# PCB-ARD-DUEBOS.net
KiCad netlist of a schematic drawn in EAGLE
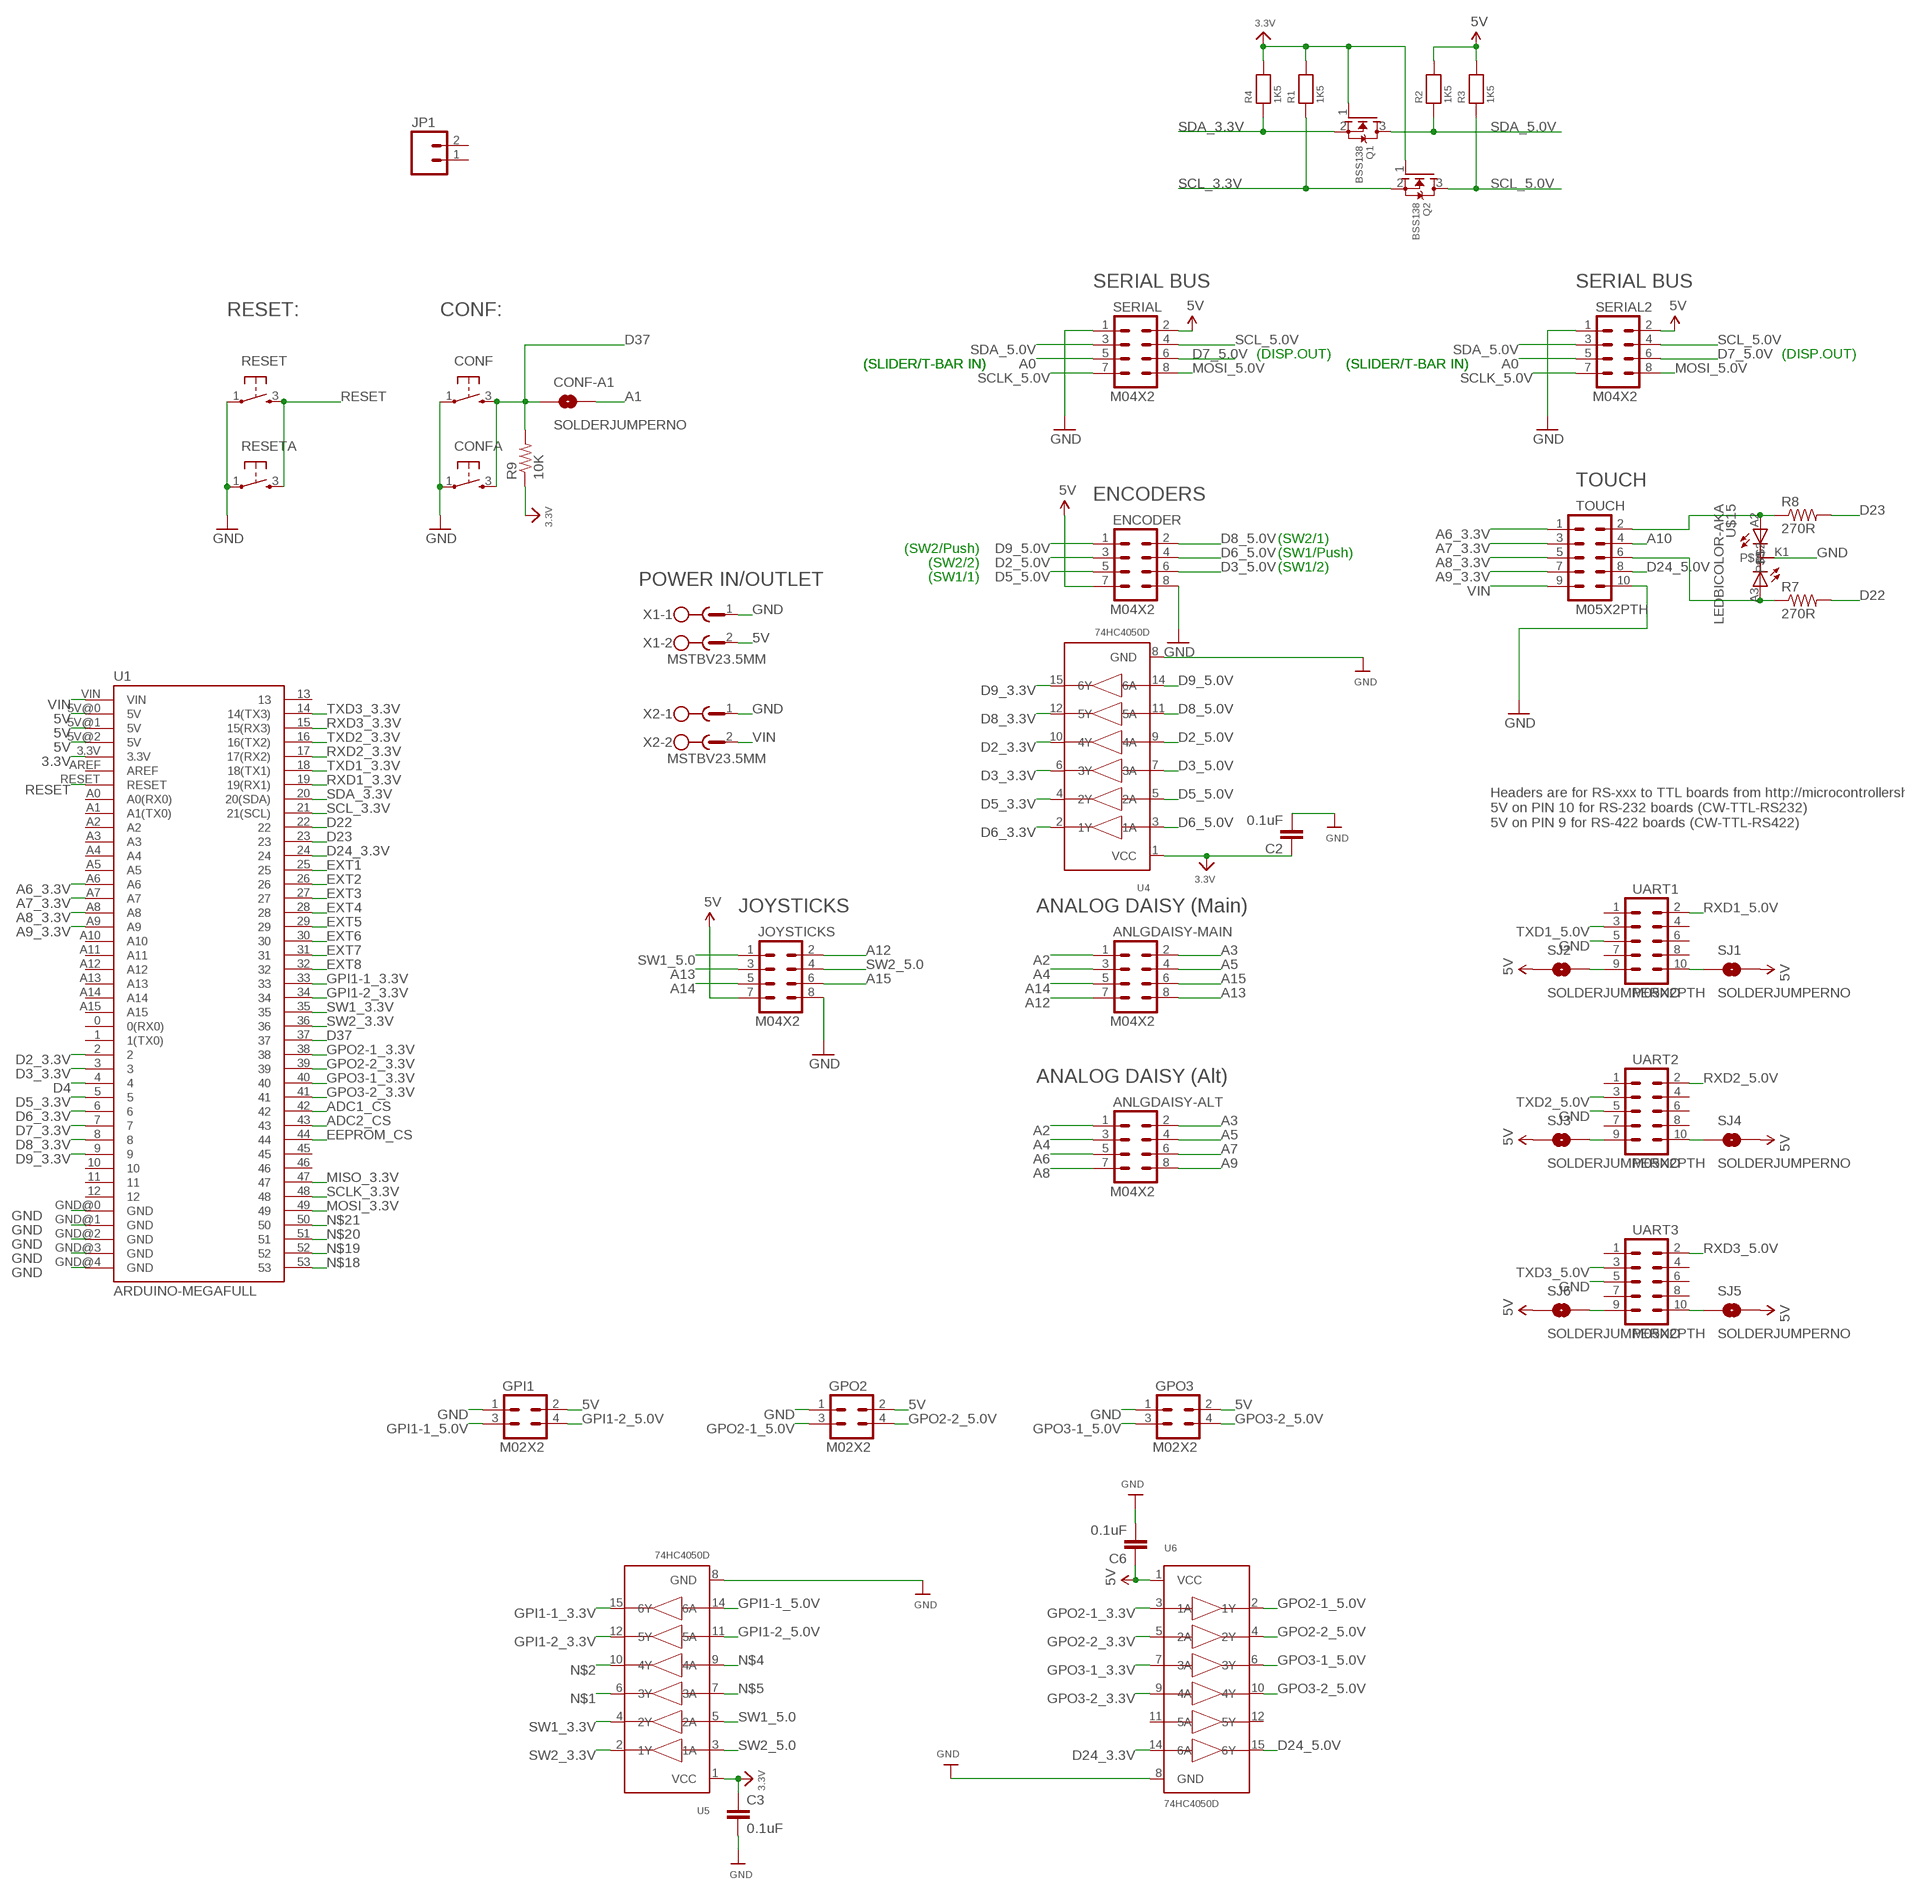
[diagram p0: schematic, sheet 1, part 1 of 2]
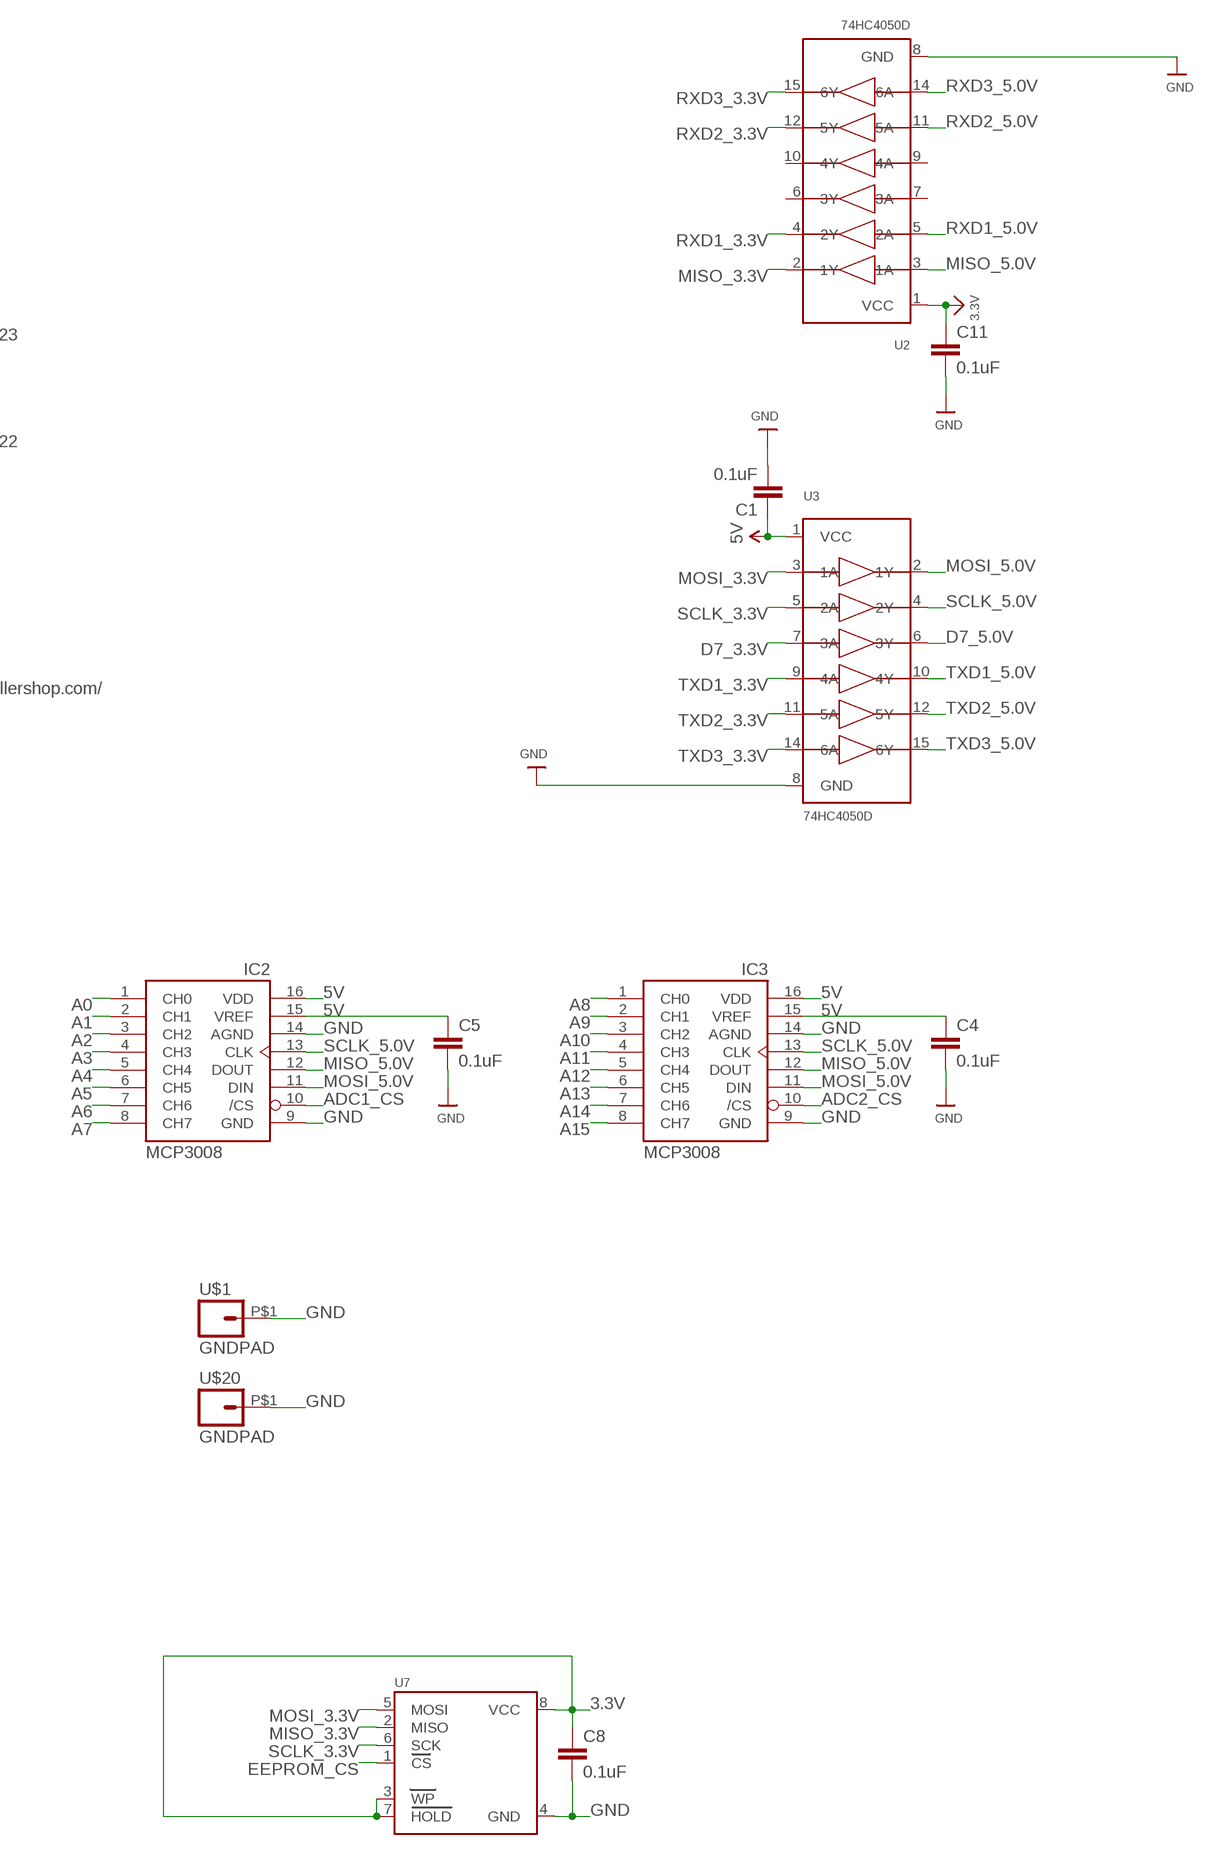
[diagram p1: schematic, sheet 1, part 2 of 2]

(export (version "E")
  (design (tool "Eeschema 10.0.6"))
  (components
    (comp (ref "ANLGDAISY-ALT")
      (value "M04X2")
      (footprint "eagle-import:2X4")
      (libsource (lib "eagle-import") (part "M04X2"))
    )
    (comp (ref "ANLGDAISY-MAIN")
      (value "M04X2")
      (footprint "eagle-import:2X4")
      (libsource (lib "eagle-import") (part "M04X2"))
    )
    (comp (ref "C1")
      (value "0.1uF")
      (footprint "eagle-import:0603-CAP")
      (libsource (lib "eagle-import") (part "CAP0603-CAP"))
    )
    (comp (ref "C2")
      (value "0.1uF")
      (footprint "eagle-import:0603-CAP")
      (libsource (lib "eagle-import") (part "CAP0603-CAP"))
    )
    (comp (ref "C3")
      (value "0.1uF")
      (footprint "eagle-import:0603-CAP")
      (libsource (lib "eagle-import") (part "CAP0603-CAP"))
    )
    (comp (ref "C4")
      (value "0.1uF")
      (footprint "eagle-import:0603-CAP")
      (libsource (lib "eagle-import") (part "CAP0603-CAP"))
    )
    (comp (ref "C5")
      (value "0.1uF")
      (footprint "eagle-import:0603-CAP")
      (libsource (lib "eagle-import") (part "CAP0603-CAP"))
    )
    (comp (ref "C6")
      (value "0.1uF")
      (footprint "eagle-import:0603-CAP")
      (libsource (lib "eagle-import") (part "CAP0603-CAP"))
    )
    (comp (ref "C8")
      (value "0.1uF")
      (footprint "eagle-import:0603-CAP")
      (libsource (lib "eagle-import") (part "CAP0603-CAP"))
    )
    (comp (ref "C11")
      (value "0.1uF")
      (footprint "eagle-import:0603-CAP")
      (libsource (lib "eagle-import") (part "CAP0603-CAP"))
    )
    (comp (ref "CONF")
      (value "TAC_SWITCH")
      (footprint "eagle-import:PUSHBUTTON")
      (libsource (lib "eagle-import") (part "TAC_SWITCH"))
    )
    (comp (ref "CONF-A1")
      (value "SOLDERJUMPERNO")
      (footprint "eagle-import:SJ_2S-NO")
      (libsource (lib "eagle-import") (part "SOLDERJUMPERNO"))
    )
    (comp (ref "CONFA")
      (value "TAC_SWITCH")
      (footprint "eagle-import:PUSHBUTTON")
      (libsource (lib "eagle-import") (part "TAC_SWITCH"))
    )
    (comp (ref "ENCODER")
      (value "M04X2")
      (footprint "eagle-import:2X4")
      (libsource (lib "eagle-import") (part "M04X2"))
    )
    (comp (ref "GPI1")
      (value "M02X2")
      (footprint "eagle-import:2X2")
      (libsource (lib "eagle-import") (part "M02X2"))
    )
    (comp (ref "GPO2")
      (value "M02X2")
      (footprint "eagle-import:2X2")
      (libsource (lib "eagle-import") (part "M02X2"))
    )
    (comp (ref "GPO3")
      (value "M02X2")
      (footprint "eagle-import:2X2")
      (libsource (lib "eagle-import") (part "M02X2"))
    )
    (comp (ref "IC2")
      (value "MCP3008SOIC")
      (footprint "eagle-import:SOIC16")
      (libsource (lib "eagle-import") (part "MCP3008SOIC"))
    )
    (comp (ref "IC3")
      (value "MCP3008SOIC")
      (footprint "eagle-import:SOIC16")
      (libsource (lib "eagle-import") (part "MCP3008SOIC"))
    )
    (comp (ref "JOYSTICKS")
      (value "M04X2")
      (footprint "eagle-import:2X4")
      (libsource (lib "eagle-import") (part "M04X2"))
    )
    (comp (ref "JP1")
      (value "M02PTH")
      (footprint "eagle-import:1X02")
      (libsource (lib "eagle-import") (part "M02PTH"))
    )
    (comp (ref "Q1")
      (value "BSS138")
      (footprint "eagle-import:SOT23-R")
      (libsource (lib "eagle-import") (part "MOSFET-NREFLOW"))
    )
    (comp (ref "Q2")
      (value "BSS138")
      (footprint "eagle-import:SOT23-R")
      (libsource (lib "eagle-import") (part "MOSFET-NREFLOW"))
    )
    (comp (ref "R1")
      (value "1K5")
      (footprint "eagle-import:0603")
      (libsource (lib "eagle-import") (part "RESISTOR0603"))
    )
    (comp (ref "R2")
      (value "1K5")
      (footprint "eagle-import:0603")
      (libsource (lib "eagle-import") (part "RESISTOR0603"))
    )
    (comp (ref "R3")
      (value "1K5")
      (footprint "eagle-import:0603")
      (libsource (lib "eagle-import") (part "RESISTOR0603"))
    )
    (comp (ref "R4")
      (value "1K5")
      (footprint "eagle-import:0603")
      (libsource (lib "eagle-import") (part "RESISTOR0603"))
    )
    (comp (ref "R7")
      (value "270R")
      (footprint "eagle-import:0603-RES")
      (libsource (lib "eagle-import") (part "RESISTOR0603-RES"))
    )
    (comp (ref "R8")
      (value "270R")
      (footprint "eagle-import:0603-RES")
      (libsource (lib "eagle-import") (part "RESISTOR0603-RES"))
    )
    (comp (ref "R9")
      (value "10K")
      (footprint "eagle-import:0603-RES")
      (libsource (lib "eagle-import") (part "RESISTOR0603-RES"))
    )
    (comp (ref "RESET")
      (value "TAC_SWITCH")
      (footprint "eagle-import:PUSHBUTTON")
      (libsource (lib "eagle-import") (part "TAC_SWITCH"))
    )
    (comp (ref "RESETA")
      (value "TAC_SWITCH")
      (footprint "eagle-import:PUSHBUTTON")
      (libsource (lib "eagle-import") (part "TAC_SWITCH"))
    )
    (comp (ref "SERIAL")
      (value "M04X2")
      (footprint "eagle-import:2X4")
      (libsource (lib "eagle-import") (part "M04X2"))
    )
    (comp (ref "SERIAL2")
      (value "M04X2")
      (footprint "eagle-import:2X4")
      (libsource (lib "eagle-import") (part "M04X2"))
    )
    (comp (ref "SJ1")
      (value "SOLDERJUMPERNO")
      (footprint "eagle-import:SJ_2S-NO")
      (libsource (lib "eagle-import") (part "SOLDERJUMPERNO"))
    )
    (comp (ref "SJ2")
      (value "SOLDERJUMPERNO")
      (footprint "eagle-import:SJ_2S-NO")
      (libsource (lib "eagle-import") (part "SOLDERJUMPERNO"))
    )
    (comp (ref "SJ3")
      (value "SOLDERJUMPERNO")
      (footprint "eagle-import:SJ_2S-NO")
      (libsource (lib "eagle-import") (part "SOLDERJUMPERNO"))
    )
    (comp (ref "SJ4")
      (value "SOLDERJUMPERNO")
      (footprint "eagle-import:SJ_2S-NO")
      (libsource (lib "eagle-import") (part "SOLDERJUMPERNO"))
    )
    (comp (ref "SJ5")
      (value "SOLDERJUMPERNO")
      (footprint "eagle-import:SJ_2S-NO")
      (libsource (lib "eagle-import") (part "SOLDERJUMPERNO"))
    )
    (comp (ref "SJ6")
      (value "SOLDERJUMPERNO")
      (footprint "eagle-import:SJ_2S-NO")
      (libsource (lib "eagle-import") (part "SOLDERJUMPERNO"))
    )
    (comp (ref "TOUCH")
      (value "M05X2PTH")
      (footprint "eagle-import:AVR_ICSP")
      (libsource (lib "eagle-import") (part "M05X2PTH"))
    )
    (comp (ref "U$1")
      (value "GNDPAD")
      (footprint "eagle-import:3.2MMPAD")
      (libsource (lib "eagle-import") (part "GNDPAD"))
    )
    (comp (ref "U$15")
      (value "LEDBICOLOR-AKA")
      (footprint "eagle-import:LED5MM-BICOLOR")
      (libsource (lib "eagle-import") (part "LEDBICOLOR-AKA"))
    )
    (comp (ref "U$20")
      (value "GNDPAD")
      (footprint "eagle-import:3.2MMPAD")
      (libsource (lib "eagle-import") (part "GNDPAD"))
    )
    (comp (ref "U1")
      (value "ARDUINO-MEGAFULL")
      (footprint "eagle-import:ARDUINO_MEGA")
      (libsource (lib "eagle-import") (part "ARDUINO-MEGAFULL"))
    )
    (comp (ref "U2")
      (value "74HC4050D")
      (footprint "eagle-import:TSSOP16")
      (libsource (lib "eagle-import") (part "74HC4050DTSSOP16"))
    )
    (comp (ref "U3")
      (value "74HC4050D")
      (footprint "eagle-import:TSSOP16")
      (libsource (lib "eagle-import") (part "74HC4050DTSSOP16"))
    )
    (comp (ref "U4")
      (value "74HC4050D")
      (footprint "eagle-import:TSSOP16")
      (libsource (lib "eagle-import") (part "74HC4050DTSSOP16"))
    )
    (comp (ref "U5")
      (value "74HC4050D")
      (footprint "eagle-import:TSSOP16")
      (libsource (lib "eagle-import") (part "74HC4050DTSSOP16"))
    )
    (comp (ref "U6")
      (value "74HC4050D")
      (footprint "eagle-import:TSSOP16")
      (libsource (lib "eagle-import") (part "74HC4050DTSSOP16"))
    )
    (comp (ref "U7")
      (value "EEPROM_SPI_AT25040ATSSOP")
      (footprint "eagle-import:TSSOP8-4.4MM")
      (libsource (lib "eagle-import") (part "EEPROM_SPI_AT25040ATSSOP"))
    )
    (comp (ref "UART1")
      (value "M05X2PTH")
      (footprint "eagle-import:AVR_ICSP")
      (libsource (lib "eagle-import") (part "M05X2PTH"))
    )
    (comp (ref "UART2")
      (value "M05X2PTH")
      (footprint "eagle-import:AVR_ICSP")
      (libsource (lib "eagle-import") (part "M05X2PTH"))
    )
    (comp (ref "UART3")
      (value "M05X2PTH")
      (footprint "eagle-import:AVR_ICSP")
      (libsource (lib "eagle-import") (part "M05X2PTH"))
    )
    (comp (ref "X1")
      (value "MSTBV23.5MM")
      (footprint "eagle-import:MSTBV2-3.5")
      (libsource (lib "eagle-import") (part "MSTBV23.5MM"))
    )
    (comp (ref "X2")
      (value "MSTBV23.5MM")
      (footprint "eagle-import:MSTBV2-3.5")
      (libsource (lib "eagle-import") (part "MSTBV23.5MM"))
    )
  )
  (nets
    (net (code "1") (name "/A0") (class "Default")
      (node (ref "IC2") (pin "1") (pinfunction "CH0_1") (pintype "input"))
      (node (ref "SERIAL") (pin "5") (pinfunction "5_5") (pintype "passive"))
      (node (ref "SERIAL2") (pin "5") (pinfunction "5_5") (pintype "passive"))
    )
    (net (code "2") (name "/A1") (class "Default")
      (node (ref "CONF-A1") (pin "2") (pinfunction "2_2") (pintype "passive"))
      (node (ref "IC2") (pin "2") (pinfunction "CH1_2") (pintype "input"))
    )
    (net (code "3") (name "/A2") (class "Default")
      (node (ref "ANLGDAISY-ALT") (pin "1") (pinfunction "1_1") (pintype "passive"))
      (node (ref "ANLGDAISY-MAIN") (pin "1") (pinfunction "1_1") (pintype "passive"))
      (node (ref "IC2") (pin "3") (pinfunction "CH2_3") (pintype "input"))
    )
    (net (code "4") (name "/A3") (class "Default")
      (node (ref "ANLGDAISY-ALT") (pin "2") (pinfunction "2_2") (pintype "passive"))
      (node (ref "ANLGDAISY-MAIN") (pin "2") (pinfunction "2_2") (pintype "passive"))
      (node (ref "IC2") (pin "4") (pinfunction "CH3_4") (pintype "input"))
    )
    (net (code "5") (name "/A4") (class "Default")
      (node (ref "ANLGDAISY-ALT") (pin "3") (pinfunction "3_3") (pintype "passive"))
      (node (ref "ANLGDAISY-MAIN") (pin "3") (pinfunction "3_3") (pintype "passive"))
      (node (ref "IC2") (pin "5") (pinfunction "CH4_5") (pintype "input"))
    )
    (net (code "6") (name "/A5") (class "Default")
      (node (ref "ANLGDAISY-ALT") (pin "4") (pinfunction "4_4") (pintype "passive"))
      (node (ref "ANLGDAISY-MAIN") (pin "4") (pinfunction "4_4") (pintype "passive"))
      (node (ref "IC2") (pin "6") (pinfunction "CH5_6") (pintype "input"))
    )
    (net (code "7") (name "/A6") (class "Default")
      (node (ref "ANLGDAISY-ALT") (pin "5") (pinfunction "5_5") (pintype "passive"))
      (node (ref "IC2") (pin "7") (pinfunction "CH6_7") (pintype "input"))
    )
    (net (code "8") (name "/A6_3.3V") (class "Default")
      (node (ref "TOUCH") (pin "1") (pinfunction "1_1") (pintype "passive"))
      (node (ref "U1") (pin "A6") (pinfunction "A6_A6") (pintype "bidirectional"))
    )
    (net (code "9") (name "/A7") (class "Default")
      (node (ref "ANLGDAISY-ALT") (pin "6") (pinfunction "6_6") (pintype "passive"))
      (node (ref "IC2") (pin "8") (pinfunction "CH7_8") (pintype "input"))
    )
    (net (code "10") (name "/A7_3.3V") (class "Default")
      (node (ref "TOUCH") (pin "3") (pinfunction "3_3") (pintype "passive"))
      (node (ref "U1") (pin "A7") (pinfunction "A7_A7") (pintype "bidirectional"))
    )
    (net (code "11") (name "/A8") (class "Default")
      (node (ref "ANLGDAISY-ALT") (pin "7") (pinfunction "7_7") (pintype "passive"))
      (node (ref "IC3") (pin "1") (pinfunction "CH0_1") (pintype "input"))
    )
    (net (code "12") (name "/A8_3.3V") (class "Default")
      (node (ref "TOUCH") (pin "5") (pinfunction "5_5") (pintype "passive"))
      (node (ref "U1") (pin "A8") (pinfunction "A8_A8") (pintype "bidirectional"))
    )
    (net (code "13") (name "/A9") (class "Default")
      (node (ref "ANLGDAISY-ALT") (pin "8") (pinfunction "8_8") (pintype "passive"))
      (node (ref "IC3") (pin "2") (pinfunction "CH1_2") (pintype "input"))
    )
    (net (code "14") (name "/A9_3.3V") (class "Default")
      (node (ref "TOUCH") (pin "7") (pinfunction "7_7") (pintype "passive"))
      (node (ref "U1") (pin "A9") (pinfunction "A9_A9") (pintype "bidirectional"))
    )
    (net (code "15") (name "/A10") (class "Default")
      (node (ref "IC3") (pin "3") (pinfunction "CH2_3") (pintype "input"))
      (node (ref "TOUCH") (pin "4") (pinfunction "4_4") (pintype "passive"))
    )
    (net (code "16") (name "/A11") (class "Default")
      (node (ref "IC3") (pin "4") (pinfunction "CH3_4") (pintype "input"))
    )
    (net (code "17") (name "/A12") (class "Default")
      (node (ref "ANLGDAISY-MAIN") (pin "7") (pinfunction "7_7") (pintype "passive"))
      (node (ref "IC3") (pin "5") (pinfunction "CH4_5") (pintype "input"))
      (node (ref "JOYSTICKS") (pin "2") (pinfunction "2_2") (pintype "passive"))
    )
    (net (code "18") (name "/A13") (class "Default")
      (node (ref "ANLGDAISY-MAIN") (pin "8") (pinfunction "8_8") (pintype "passive"))
      (node (ref "IC3") (pin "6") (pinfunction "CH5_6") (pintype "input"))
      (node (ref "JOYSTICKS") (pin "3") (pinfunction "3_3") (pintype "passive"))
    )
    (net (code "19") (name "/A14") (class "Default")
      (node (ref "ANLGDAISY-MAIN") (pin "5") (pinfunction "5_5") (pintype "passive"))
      (node (ref "IC3") (pin "7") (pinfunction "CH6_7") (pintype "input"))
      (node (ref "JOYSTICKS") (pin "5") (pinfunction "5_5") (pintype "passive"))
    )
    (net (code "20") (name "/A15") (class "Default")
      (node (ref "ANLGDAISY-MAIN") (pin "6") (pinfunction "6_6") (pintype "passive"))
      (node (ref "IC3") (pin "8") (pinfunction "CH7_8") (pintype "input"))
      (node (ref "JOYSTICKS") (pin "6") (pinfunction "6_6") (pintype "passive"))
    )
    (net (code "21") (name "/ADC1_CS") (class "Default")
      (node (ref "IC2") (pin "10") (pinfunction "/CS_10") (pintype "input"))
      (node (ref "U1") (pin "42") (pinfunction "42_42") (pintype "bidirectional"))
    )
    (net (code "22") (name "/ADC2_CS") (class "Default")
      (node (ref "IC3") (pin "10") (pinfunction "/CS_10") (pintype "input"))
      (node (ref "U1") (pin "43") (pinfunction "43_43") (pintype "bidirectional"))
    )
    (net (code "23") (name "/D2_3.3V") (class "Default")
      (node (ref "U1") (pin "2") (pinfunction "2_2") (pintype "bidirectional"))
      (node (ref "U4") (pin "10") (pinfunction "4Y_10") (pintype "bidirectional"))
    )
    (net (code "24") (name "/D2_5.0V") (class "Default")
      (node (ref "ENCODER") (pin "3") (pinfunction "3_3") (pintype "passive"))
      (node (ref "U4") (pin "9") (pinfunction "4A_9") (pintype "bidirectional"))
    )
    (net (code "25") (name "/D3_3.3V") (class "Default")
      (node (ref "U1") (pin "3") (pinfunction "3_3") (pintype "bidirectional"))
      (node (ref "U4") (pin "6") (pinfunction "3Y_6") (pintype "bidirectional"))
    )
    (net (code "26") (name "/D3_5.0V") (class "Default")
      (node (ref "ENCODER") (pin "6") (pinfunction "6_6") (pintype "passive"))
      (node (ref "U4") (pin "7") (pinfunction "3A_7") (pintype "bidirectional"))
    )
    (net (code "27") (name "/D4") (class "Default")
      (node (ref "U1") (pin "4") (pinfunction "4_4") (pintype "bidirectional"))
    )
    (net (code "28") (name "/D5_3.3V") (class "Default")
      (node (ref "U1") (pin "5") (pinfunction "5_5") (pintype "bidirectional"))
      (node (ref "U4") (pin "4") (pinfunction "2Y_4") (pintype "bidirectional"))
    )
    (net (code "29") (name "/D5_5.0V") (class "Default")
      (node (ref "ENCODER") (pin "5") (pinfunction "5_5") (pintype "passive"))
      (node (ref "U4") (pin "5") (pinfunction "2A_5") (pintype "bidirectional"))
    )
    (net (code "30") (name "/D6_3.3V") (class "Default")
      (node (ref "U1") (pin "6") (pinfunction "6_6") (pintype "bidirectional"))
      (node (ref "U4") (pin "2") (pinfunction "1Y_2") (pintype "bidirectional"))
    )
    (net (code "31") (name "/D6_5.0V") (class "Default")
      (node (ref "ENCODER") (pin "4") (pinfunction "4_4") (pintype "passive"))
      (node (ref "U4") (pin "3") (pinfunction "1A_3") (pintype "bidirectional"))
    )
    (net (code "32") (name "/D7_3.3V") (class "Default")
      (node (ref "U1") (pin "7") (pinfunction "7_7") (pintype "bidirectional"))
      (node (ref "U3") (pin "7") (pinfunction "3A_7") (pintype "bidirectional"))
    )
    (net (code "33") (name "/D7_5.0V") (class "Default")
      (node (ref "SERIAL") (pin "6") (pinfunction "6_6") (pintype "passive"))
      (node (ref "SERIAL2") (pin "6") (pinfunction "6_6") (pintype "passive"))
      (node (ref "U3") (pin "6") (pinfunction "3Y_6") (pintype "bidirectional"))
    )
    (net (code "34") (name "/D8_3.3V") (class "Default")
      (node (ref "U1") (pin "8") (pinfunction "8_8") (pintype "bidirectional"))
      (node (ref "U4") (pin "12") (pinfunction "5Y_12") (pintype "bidirectional"))
    )
    (net (code "35") (name "/D8_5.0V") (class "Default")
      (node (ref "ENCODER") (pin "2") (pinfunction "2_2") (pintype "passive"))
      (node (ref "U4") (pin "11") (pinfunction "5A_11") (pintype "bidirectional"))
    )
    (net (code "36") (name "/D9_3.3V") (class "Default")
      (node (ref "U1") (pin "9") (pinfunction "9_9") (pintype "bidirectional"))
      (node (ref "U4") (pin "15") (pinfunction "6Y_15") (pintype "bidirectional"))
    )
    (net (code "37") (name "/D9_5.0V") (class "Default")
      (node (ref "ENCODER") (pin "1") (pinfunction "1_1") (pintype "passive"))
      (node (ref "U4") (pin "14") (pinfunction "6A_14") (pintype "bidirectional"))
    )
    (net (code "38") (name "/D22") (class "Default")
      (node (ref "R7") (pin "2") (pinfunction "2_2") (pintype "passive"))
      (node (ref "U1") (pin "22") (pinfunction "22_22") (pintype "bidirectional"))
    )
    (net (code "39") (name "/D23") (class "Default")
      (node (ref "R8") (pin "2") (pinfunction "2_2") (pintype "passive"))
      (node (ref "U1") (pin "23") (pinfunction "23_23") (pintype "bidirectional"))
    )
    (net (code "40") (name "/D24_3.3V") (class "Default")
      (node (ref "U1") (pin "24") (pinfunction "24_24") (pintype "bidirectional"))
      (node (ref "U6") (pin "14") (pinfunction "6A_14") (pintype "bidirectional"))
    )
    (net (code "41") (name "/D24_5.0V") (class "Default")
      (node (ref "TOUCH") (pin "8") (pinfunction "8_8") (pintype "passive"))
      (node (ref "U6") (pin "15") (pinfunction "6Y_15") (pintype "bidirectional"))
    )
    (net (code "42") (name "/D37") (class "Default")
      (node (ref "CONF") (pin "3") (pinfunction "3_3") (pintype "passive"))
      (node (ref "CONF-A1") (pin "1") (pinfunction "1_1") (pintype "passive"))
      (node (ref "CONFA") (pin "3") (pinfunction "3_3") (pintype "passive"))
      (node (ref "R9") (pin "2") (pinfunction "2_2") (pintype "passive"))
      (node (ref "U1") (pin "37") (pinfunction "37_37") (pintype "bidirectional"))
    )
    (net (code "43") (name "/EEPROM_CS") (class "Default")
      (node (ref "U1") (pin "44") (pinfunction "44_44") (pintype "bidirectional"))
      (node (ref "U7") (pin "1") (pinfunction "CS_1") (pintype "bidirectional"))
    )
    (net (code "44") (name "/EXT1") (class "Default")
      (node (ref "U1") (pin "25") (pinfunction "25_25") (pintype "bidirectional"))
    )
    (net (code "45") (name "/EXT2") (class "Default")
      (node (ref "U1") (pin "26") (pinfunction "26_26") (pintype "bidirectional"))
    )
    (net (code "46") (name "/EXT3") (class "Default")
      (node (ref "U1") (pin "27") (pinfunction "27_27") (pintype "bidirectional"))
    )
    (net (code "47") (name "/EXT4") (class "Default")
      (node (ref "U1") (pin "28") (pinfunction "28_28") (pintype "bidirectional"))
    )
    (net (code "48") (name "/EXT5") (class "Default")
      (node (ref "U1") (pin "29") (pinfunction "29_29") (pintype "bidirectional"))
    )
    (net (code "49") (name "/EXT6") (class "Default")
      (node (ref "U1") (pin "30") (pinfunction "30_30") (pintype "bidirectional"))
    )
    (net (code "50") (name "/EXT7") (class "Default")
      (node (ref "U1") (pin "31") (pinfunction "31_31") (pintype "bidirectional"))
    )
    (net (code "51") (name "/EXT8") (class "Default")
      (node (ref "U1") (pin "32") (pinfunction "32_32") (pintype "bidirectional"))
    )
    (net (code "52") (name "/GPI1-1_3.3V") (class "Default")
      (node (ref "U1") (pin "33") (pinfunction "33_33") (pintype "bidirectional"))
      (node (ref "U5") (pin "15") (pinfunction "6Y_15") (pintype "bidirectional"))
    )
    (net (code "53") (name "/GPI1-1_5.0V") (class "Default")
      (node (ref "GPI1") (pin "3") (pinfunction "3_3") (pintype "passive"))
      (node (ref "U5") (pin "14") (pinfunction "6A_14") (pintype "bidirectional"))
    )
    (net (code "54") (name "/GPI1-2_3.3V") (class "Default")
      (node (ref "U1") (pin "34") (pinfunction "34_34") (pintype "bidirectional"))
      (node (ref "U5") (pin "12") (pinfunction "5Y_12") (pintype "bidirectional"))
    )
    (net (code "55") (name "/GPI1-2_5.0V") (class "Default")
      (node (ref "GPI1") (pin "4") (pinfunction "4_4") (pintype "passive"))
      (node (ref "U5") (pin "11") (pinfunction "5A_11") (pintype "bidirectional"))
    )
    (net (code "56") (name "/GPO2-1_3.3V") (class "Default")
      (node (ref "U1") (pin "38") (pinfunction "38_38") (pintype "bidirectional"))
      (node (ref "U6") (pin "3") (pinfunction "1A_3") (pintype "bidirectional"))
    )
    (net (code "57") (name "/GPO2-1_5.0V") (class "Default")
      (node (ref "GPO2") (pin "3") (pinfunction "3_3") (pintype "passive"))
      (node (ref "U6") (pin "2") (pinfunction "1Y_2") (pintype "bidirectional"))
    )
    (net (code "58") (name "/GPO2-2_3.3V") (class "Default")
      (node (ref "U1") (pin "39") (pinfunction "39_39") (pintype "bidirectional"))
      (node (ref "U6") (pin "5") (pinfunction "2A_5") (pintype "bidirectional"))
    )
    (net (code "59") (name "/GPO2-2_5.0V") (class "Default")
      (node (ref "GPO2") (pin "4") (pinfunction "4_4") (pintype "passive"))
      (node (ref "U6") (pin "4") (pinfunction "2Y_4") (pintype "bidirectional"))
    )
    (net (code "60") (name "/GPO3-1_3.3V") (class "Default")
      (node (ref "U1") (pin "40") (pinfunction "40_40") (pintype "bidirectional"))
      (node (ref "U6") (pin "7") (pinfunction "3A_7") (pintype "bidirectional"))
    )
    (net (code "61") (name "/GPO3-1_5.0V") (class "Default")
      (node (ref "GPO3") (pin "3") (pinfunction "3_3") (pintype "passive"))
      (node (ref "U6") (pin "6") (pinfunction "3Y_6") (pintype "bidirectional"))
    )
    (net (code "62") (name "/GPO3-2_3.3V") (class "Default")
      (node (ref "U1") (pin "41") (pinfunction "41_41") (pintype "bidirectional"))
      (node (ref "U6") (pin "9") (pinfunction "4A_9") (pintype "bidirectional"))
    )
    (net (code "63") (name "/GPO3-2_5.0V") (class "Default")
      (node (ref "GPO3") (pin "4") (pinfunction "4_4") (pintype "passive"))
      (node (ref "U6") (pin "10") (pinfunction "4Y_10") (pintype "bidirectional"))
    )
    (net (code "64") (name "/MISO_3.3V") (class "Default")
      (node (ref "U1") (pin "47") (pinfunction "47_47") (pintype "bidirectional"))
      (node (ref "U2") (pin "2") (pinfunction "1Y_2") (pintype "bidirectional"))
      (node (ref "U7") (pin "2") (pinfunction "MISO_2") (pintype "bidirectional"))
    )
    (net (code "65") (name "/MISO_5.0V") (class "Default")
      (node (ref "IC2") (pin "12") (pinfunction "DOUT_12") (pintype "output"))
      (node (ref "IC3") (pin "12") (pinfunction "DOUT_12") (pintype "output"))
      (node (ref "U2") (pin "3") (pinfunction "1A_3") (pintype "bidirectional"))
    )
    (net (code "66") (name "/MOSI_3.3V") (class "Default")
      (node (ref "U1") (pin "49") (pinfunction "49_49") (pintype "bidirectional"))
      (node (ref "U3") (pin "3") (pinfunction "1A_3") (pintype "bidirectional"))
      (node (ref "U7") (pin "5") (pinfunction "MOSI_5") (pintype "bidirectional"))
    )
    (net (code "67") (name "/MOSI_5.0V") (class "Default")
      (node (ref "IC2") (pin "11") (pinfunction "DIN_11") (pintype "input"))
      (node (ref "IC3") (pin "11") (pinfunction "DIN_11") (pintype "input"))
      (node (ref "SERIAL") (pin "8") (pinfunction "8_8") (pintype "passive"))
      (node (ref "SERIAL2") (pin "8") (pinfunction "8_8") (pintype "passive"))
      (node (ref "U3") (pin "2") (pinfunction "1Y_2") (pintype "bidirectional"))
    )
    (net (code "68") (name "/N$1") (class "Default")
      (node (ref "U5") (pin "6") (pinfunction "3Y_6") (pintype "bidirectional"))
    )
    (net (code "69") (name "/N$2") (class "Default")
      (node (ref "U5") (pin "10") (pinfunction "4Y_10") (pintype "bidirectional"))
    )
    (net (code "70") (name "/N$4") (class "Default")
      (node (ref "U5") (pin "9") (pinfunction "4A_9") (pintype "bidirectional"))
    )
    (net (code "71") (name "/N$5") (class "Default")
      (node (ref "U5") (pin "7") (pinfunction "3A_7") (pintype "bidirectional"))
    )
    (net (code "72") (name "/N$18") (class "Default")
      (node (ref "U1") (pin "53") (pinfunction "53_53") (pintype "bidirectional"))
    )
    (net (code "73") (name "/N$19") (class "Default")
      (node (ref "U1") (pin "52") (pinfunction "52_52") (pintype "bidirectional"))
    )
    (net (code "74") (name "/N$20") (class "Default")
      (node (ref "U1") (pin "51") (pinfunction "51_51") (pintype "bidirectional"))
    )
    (net (code "75") (name "/N$21") (class "Default")
      (node (ref "U1") (pin "50") (pinfunction "50_50") (pintype "bidirectional"))
    )
    (net (code "76") (name "/RESET") (class "Default")
      (node (ref "RESET") (pin "3") (pinfunction "3_3") (pintype "passive"))
      (node (ref "RESETA") (pin "3") (pinfunction "3_3") (pintype "passive"))
      (node (ref "U1") (pin "RESET") (pinfunction "RESET_RESET") (pintype "bidirectional"))
    )
    (net (code "77") (name "/RXD1_3.3V") (class "Default")
      (node (ref "U1") (pin "19") (pinfunction "19(RX1)_19") (pintype "bidirectional"))
      (node (ref "U2") (pin "4") (pinfunction "2Y_4") (pintype "bidirectional"))
    )
    (net (code "78") (name "/RXD1_5.0V") (class "Default")
      (node (ref "U2") (pin "5") (pinfunction "2A_5") (pintype "bidirectional"))
      (node (ref "UART1") (pin "2") (pinfunction "2_2") (pintype "passive"))
    )
    (net (code "79") (name "/RXD2_3.3V") (class "Default")
      (node (ref "U1") (pin "17") (pinfunction "17(RX2)_17") (pintype "bidirectional"))
      (node (ref "U2") (pin "12") (pinfunction "5Y_12") (pintype "bidirectional"))
    )
    (net (code "80") (name "/RXD2_5.0V") (class "Default")
      (node (ref "U2") (pin "11") (pinfunction "5A_11") (pintype "bidirectional"))
      (node (ref "UART2") (pin "2") (pinfunction "2_2") (pintype "passive"))
    )
    (net (code "81") (name "/RXD3_3.3V") (class "Default")
      (node (ref "U1") (pin "15") (pinfunction "15(RX3)_15") (pintype "bidirectional"))
      (node (ref "U2") (pin "15") (pinfunction "6Y_15") (pintype "bidirectional"))
    )
    (net (code "82") (name "/RXD3_5.0V") (class "Default")
      (node (ref "U2") (pin "14") (pinfunction "6A_14") (pintype "bidirectional"))
      (node (ref "UART3") (pin "2") (pinfunction "2_2") (pintype "passive"))
    )
    (net (code "83") (name "/SCLK_3.3V") (class "Default")
      (node (ref "U1") (pin "48") (pinfunction "48_48") (pintype "bidirectional"))
      (node (ref "U3") (pin "5") (pinfunction "2A_5") (pintype "bidirectional"))
      (node (ref "U7") (pin "6") (pinfunction "SCK_6") (pintype "bidirectional"))
    )
    (net (code "84") (name "/SCLK_5.0V") (class "Default")
      (node (ref "IC2") (pin "13") (pinfunction "CLK_13") (pintype "input"))
      (node (ref "IC3") (pin "13") (pinfunction "CLK_13") (pintype "input"))
      (node (ref "SERIAL") (pin "7") (pinfunction "7_7") (pintype "passive"))
      (node (ref "SERIAL2") (pin "7") (pinfunction "7_7") (pintype "passive"))
      (node (ref "U3") (pin "4") (pinfunction "2Y_4") (pintype "bidirectional"))
    )
    (net (code "85") (name "/SCL_3.3V") (class "Default")
      (node (ref "Q2") (pin "2") (pinfunction "S_2") (pintype "bidirectional"))
      (node (ref "R1") (pin "1") (pinfunction "1_1") (pintype "passive"))
      (node (ref "U1") (pin "21") (pinfunction "21(SCL)_21") (pintype "bidirectional"))
    )
    (net (code "86") (name "/SCL_5.0V") (class "Default")
      (node (ref "Q2") (pin "3") (pinfunction "D_3") (pintype "bidirectional"))
      (node (ref "R3") (pin "1") (pinfunction "1_1") (pintype "passive"))
      (node (ref "SERIAL") (pin "4") (pinfunction "4_4") (pintype "passive"))
      (node (ref "SERIAL2") (pin "4") (pinfunction "4_4") (pintype "passive"))
    )
    (net (code "87") (name "/SDA_3.3V") (class "Default")
      (node (ref "Q1") (pin "2") (pinfunction "S_2") (pintype "bidirectional"))
      (node (ref "R4") (pin "1") (pinfunction "1_1") (pintype "passive"))
      (node (ref "U1") (pin "20") (pinfunction "20(SDA)_20") (pintype "bidirectional"))
    )
    (net (code "88") (name "/SDA_5.0V") (class "Default")
      (node (ref "Q1") (pin "3") (pinfunction "D_3") (pintype "bidirectional"))
      (node (ref "R2") (pin "1") (pinfunction "1_1") (pintype "passive"))
      (node (ref "SERIAL") (pin "3") (pinfunction "3_3") (pintype "passive"))
      (node (ref "SERIAL2") (pin "3") (pinfunction "3_3") (pintype "passive"))
    )
    (net (code "89") (name "/SW1_3.3V") (class "Default")
      (node (ref "U1") (pin "35") (pinfunction "35_35") (pintype "bidirectional"))
      (node (ref "U5") (pin "4") (pinfunction "2Y_4") (pintype "bidirectional"))
    )
    (net (code "90") (name "/SW1_5.0") (class "Default")
      (node (ref "JOYSTICKS") (pin "1") (pinfunction "1_1") (pintype "passive"))
      (node (ref "U5") (pin "5") (pinfunction "2A_5") (pintype "bidirectional"))
    )
    (net (code "91") (name "/SW2_3.3V") (class "Default")
      (node (ref "U1") (pin "36") (pinfunction "36_36") (pintype "bidirectional"))
      (node (ref "U5") (pin "2") (pinfunction "1Y_2") (pintype "bidirectional"))
    )
    (net (code "92") (name "/SW2_5.0") (class "Default")
      (node (ref "JOYSTICKS") (pin "4") (pinfunction "4_4") (pintype "passive"))
      (node (ref "U5") (pin "3") (pinfunction "1A_3") (pintype "bidirectional"))
    )
    (net (code "93") (name "/TXD1_3.3V") (class "Default")
      (node (ref "U1") (pin "18") (pinfunction "18(TX1)_18") (pintype "bidirectional"))
      (node (ref "U3") (pin "9") (pinfunction "4A_9") (pintype "bidirectional"))
    )
    (net (code "94") (name "/TXD1_5.0V") (class "Default")
      (node (ref "U3") (pin "10") (pinfunction "4Y_10") (pintype "bidirectional"))
      (node (ref "UART1") (pin "3") (pinfunction "3_3") (pintype "passive"))
    )
    (net (code "95") (name "/TXD2_3.3V") (class "Default")
      (node (ref "U1") (pin "16") (pinfunction "16(TX2)_16") (pintype "bidirectional"))
      (node (ref "U3") (pin "11") (pinfunction "5A_11") (pintype "bidirectional"))
    )
    (net (code "96") (name "/TXD2_5.0V") (class "Default")
      (node (ref "U3") (pin "12") (pinfunction "5Y_12") (pintype "bidirectional"))
      (node (ref "UART2") (pin "3") (pinfunction "3_3") (pintype "passive"))
    )
    (net (code "97") (name "/TXD3_3.3V") (class "Default")
      (node (ref "U1") (pin "14") (pinfunction "14(TX3)_14") (pintype "bidirectional"))
      (node (ref "U3") (pin "14") (pinfunction "6A_14") (pintype "bidirectional"))
    )
    (net (code "98") (name "/TXD3_5.0V") (class "Default")
      (node (ref "U3") (pin "15") (pinfunction "6Y_15") (pintype "bidirectional"))
      (node (ref "UART3") (pin "3") (pinfunction "3_3") (pintype "passive"))
    )
    (net (code "99") (name "/VIN") (class "Default")
      (node (ref "TOUCH") (pin "9") (pinfunction "9_9") (pintype "passive"))
      (node (ref "U1") (pin "VIN") (pinfunction "VIN_VIN") (pintype "bidirectional"))
      (node (ref "X2") (pin "2") (pinfunction "1_2") (pintype "passive"))
    )
    (net (code "100") (name "3.3V") (class "Default")
      (node (ref "C11") (pin "1") (pinfunction "1_1") (pintype "passive"))
      (node (ref "C2") (pin "1") (pinfunction "1_1") (pintype "passive"))
      (node (ref "C3") (pin "1") (pinfunction "1_1") (pintype "passive"))
      (node (ref "C8") (pin "1") (pinfunction "1_1") (pintype "passive"))
      (node (ref "Q1") (pin "1") (pinfunction "G_1") (pintype "bidirectional"))
      (node (ref "Q2") (pin "1") (pinfunction "G_1") (pintype "bidirectional"))
      (node (ref "R1") (pin "2") (pinfunction "2_2") (pintype "passive"))
      (node (ref "R4") (pin "2") (pinfunction "2_2") (pintype "passive"))
      (node (ref "R9") (pin "1") (pinfunction "1_1") (pintype "passive"))
      (node (ref "U1") (pin "3.3V") (pinfunction "3.3V_3.3V") (pintype "bidirectional"))
      (node (ref "U2") (pin "1") (pinfunction "VCC_1") (pintype "bidirectional"))
      (node (ref "U4") (pin "1") (pinfunction "VCC_1") (pintype "bidirectional"))
      (node (ref "U5") (pin "1") (pinfunction "VCC_1") (pintype "bidirectional"))
      (node (ref "U7") (pin "3") (pinfunction "WP_3") (pintype "bidirectional"))
      (node (ref "U7") (pin "7") (pinfunction "HOLD_7") (pintype "bidirectional"))
      (node (ref "U7") (pin "8") (pinfunction "VCC_8") (pintype "power_in"))
    )
    (net (code "101") (name "5V") (class "Default")
      (node (ref "C1") (pin "1") (pinfunction "1_1") (pintype "passive"))
      (node (ref "C4") (pin "1") (pinfunction "1_1") (pintype "passive"))
      (node (ref "C5") (pin "1") (pinfunction "1_1") (pintype "passive"))
      (node (ref "C6") (pin "1") (pinfunction "1_1") (pintype "passive"))
      (node (ref "ENCODER") (pin "7") (pinfunction "7_7") (pintype "passive"))
      (node (ref "GPI1") (pin "2") (pinfunction "2_2") (pintype "passive"))
      (node (ref "GPO2") (pin "2") (pinfunction "2_2") (pintype "passive"))
      (node (ref "GPO3") (pin "2") (pinfunction "2_2") (pintype "passive"))
      (node (ref "IC2") (pin "15") (pinfunction "VREF_15") (pintype "input"))
      (node (ref "IC2") (pin "16") (pinfunction "VDD_16") (pintype "power_in"))
      (node (ref "IC3") (pin "15") (pinfunction "VREF_15") (pintype "input"))
      (node (ref "IC3") (pin "16") (pinfunction "VDD_16") (pintype "power_in"))
      (node (ref "JOYSTICKS") (pin "7") (pinfunction "7_7") (pintype "passive"))
      (node (ref "R2") (pin "2") (pinfunction "2_2") (pintype "passive"))
      (node (ref "R3") (pin "2") (pinfunction "2_2") (pintype "passive"))
      (node (ref "SERIAL") (pin "2") (pinfunction "2_2") (pintype "passive"))
      (node (ref "SERIAL2") (pin "2") (pinfunction "2_2") (pintype "passive"))
      (node (ref "SJ1") (pin "2") (pinfunction "2_2") (pintype "passive"))
      (node (ref "SJ2") (pin "1") (pinfunction "1_1") (pintype "passive"))
      (node (ref "SJ3") (pin "1") (pinfunction "1_1") (pintype "passive"))
      (node (ref "SJ4") (pin "2") (pinfunction "2_2") (pintype "passive"))
      (node (ref "SJ5") (pin "2") (pinfunction "2_2") (pintype "passive"))
      (node (ref "SJ6") (pin "1") (pinfunction "1_1") (pintype "passive"))
      (node (ref "U1") (pin "5V@0") (pinfunction "5V_5V@0") (pintype "bidirectional"))
      (node (ref "U1") (pin "5V@1") (pinfunction "5V_5V@1") (pintype "bidirectional"))
      (node (ref "U1") (pin "5V@2") (pinfunction "5V_5V@2") (pintype "bidirectional"))
      (node (ref "U3") (pin "1") (pinfunction "VCC_1") (pintype "bidirectional"))
      (node (ref "U6") (pin "1") (pinfunction "VCC_1") (pintype "bidirectional"))
      (node (ref "X1") (pin "2") (pinfunction "1_2") (pintype "passive"))
    )
    (net (code "102") (name "GND") (class "Default")
      (node (ref "C1") (pin "2") (pinfunction "2_2") (pintype "passive"))
      (node (ref "C11") (pin "2") (pinfunction "2_2") (pintype "passive"))
      (node (ref "C2") (pin "2") (pinfunction "2_2") (pintype "passive"))
      (node (ref "C3") (pin "2") (pinfunction "2_2") (pintype "passive"))
      (node (ref "C4") (pin "2") (pinfunction "2_2") (pintype "passive"))
      (node (ref "C5") (pin "2") (pinfunction "2_2") (pintype "passive"))
      (node (ref "C6") (pin "2") (pinfunction "2_2") (pintype "passive"))
      (node (ref "C8") (pin "2") (pinfunction "2_2") (pintype "passive"))
      (node (ref "CONF") (pin "1") (pinfunction "1_1") (pintype "passive"))
      (node (ref "CONFA") (pin "1") (pinfunction "1_1") (pintype "passive"))
      (node (ref "ENCODER") (pin "8") (pinfunction "8_8") (pintype "passive"))
      (node (ref "GPI1") (pin "1") (pinfunction "1_1") (pintype "passive"))
      (node (ref "GPO2") (pin "1") (pinfunction "1_1") (pintype "passive"))
      (node (ref "GPO3") (pin "1") (pinfunction "1_1") (pintype "passive"))
      (node (ref "IC2") (pin "14") (pinfunction "AGND_14") (pintype "power_in"))
      (node (ref "IC2") (pin "9") (pinfunction "GND_9") (pintype "power_in"))
      (node (ref "IC3") (pin "14") (pinfunction "AGND_14") (pintype "power_in"))
      (node (ref "IC3") (pin "9") (pinfunction "GND_9") (pintype "power_in"))
      (node (ref "JOYSTICKS") (pin "8") (pinfunction "8_8") (pintype "passive"))
      (node (ref "RESET") (pin "1") (pinfunction "1_1") (pintype "passive"))
      (node (ref "RESETA") (pin "1") (pinfunction "1_1") (pintype "passive"))
      (node (ref "SERIAL") (pin "1") (pinfunction "1_1") (pintype "passive"))
      (node (ref "SERIAL2") (pin "1") (pinfunction "1_1") (pintype "passive"))
      (node (ref "TOUCH") (pin "10") (pinfunction "10_10") (pintype "passive"))
      (node (ref "U$1") (pin "P$1") (pinfunction "1_P$1") (pintype "passive"))
      (node (ref "U$15") (pin "K1") (pinfunction "P$1_K1") (pintype "bidirectional"))
      (node (ref "U$20") (pin "P$1") (pinfunction "1_P$1") (pintype "passive"))
      (node (ref "U1") (pin "GND@0") (pinfunction "GND_GND@0") (pintype "bidirectional"))
      (node (ref "U1") (pin "GND@1") (pinfunction "GND_GND@1") (pintype "bidirectional"))
      (node (ref "U1") (pin "GND@2") (pinfunction "GND_GND@2") (pintype "bidirectional"))
      (node (ref "U1") (pin "GND@3") (pinfunction "GND_GND@3") (pintype "bidirectional"))
      (node (ref "U1") (pin "GND@4") (pinfunction "GND_GND@4") (pintype "bidirectional"))
      (node (ref "U2") (pin "8") (pinfunction "GND_8") (pintype "bidirectional"))
      (node (ref "U3") (pin "8") (pinfunction "GND_8") (pintype "bidirectional"))
      (node (ref "U4") (pin "8") (pinfunction "GND_8") (pintype "bidirectional"))
      (node (ref "U5") (pin "8") (pinfunction "GND_8") (pintype "bidirectional"))
      (node (ref "U6") (pin "8") (pinfunction "GND_8") (pintype "bidirectional"))
      (node (ref "U7") (pin "4") (pinfunction "GND_4") (pintype "power_in"))
      (node (ref "UART1") (pin "5") (pinfunction "5_5") (pintype "passive"))
      (node (ref "UART2") (pin "5") (pinfunction "5_5") (pintype "passive"))
      (node (ref "UART3") (pin "5") (pinfunction "5_5") (pintype "passive"))
      (node (ref "X1") (pin "1") (pinfunction "1_1") (pintype "passive"))
      (node (ref "X2") (pin "1") (pinfunction "1_1") (pintype "passive"))
    )
    (net (code "103") (name "Net-(SJ1-Pad1)") (class "Default")
      (node (ref "SJ1") (pin "1") (pinfunction "1_1") (pintype "passive"))
      (node (ref "UART1") (pin "10") (pinfunction "10_10") (pintype "passive"))
    )
    (net (code "104") (name "Net-(SJ2-Pad2)") (class "Default")
      (node (ref "SJ2") (pin "2") (pinfunction "2_2") (pintype "passive"))
      (node (ref "UART1") (pin "9") (pinfunction "9_9") (pintype "passive"))
    )
    (net (code "105") (name "Net-(SJ3-Pad2)") (class "Default")
      (node (ref "SJ3") (pin "2") (pinfunction "2_2") (pintype "passive"))
      (node (ref "UART2") (pin "9") (pinfunction "9_9") (pintype "passive"))
    )
    (net (code "106") (name "Net-(SJ4-Pad1)") (class "Default")
      (node (ref "SJ4") (pin "1") (pinfunction "1_1") (pintype "passive"))
      (node (ref "UART2") (pin "10") (pinfunction "10_10") (pintype "passive"))
    )
    (net (code "107") (name "Net-(SJ5-Pad1)") (class "Default")
      (node (ref "SJ5") (pin "1") (pinfunction "1_1") (pintype "passive"))
      (node (ref "UART3") (pin "10") (pinfunction "10_10") (pintype "passive"))
    )
    (net (code "108") (name "Net-(SJ6-Pad2)") (class "Default")
      (node (ref "SJ6") (pin "2") (pinfunction "2_2") (pintype "passive"))
      (node (ref "UART3") (pin "9") (pinfunction "9_9") (pintype "passive"))
    )
    (net (code "109") (name "Net-(U$15-P$2)") (class "Default")
      (node (ref "R8") (pin "1") (pinfunction "1_1") (pintype "passive"))
      (node (ref "TOUCH") (pin "2") (pinfunction "2_2") (pintype "passive"))
      (node (ref "U$15") (pin "A2") (pinfunction "P$2_A2") (pintype "bidirectional"))
    )
    (net (code "110") (name "Net-(U$15-P$3)") (class "Default")
      (node (ref "R7") (pin "1") (pinfunction "1_1") (pintype "passive"))
      (node (ref "TOUCH") (pin "6") (pinfunction "6_6") (pintype "passive"))
      (node (ref "U$15") (pin "A3") (pinfunction "P$3_A3") (pintype "bidirectional"))
    )
    (net (code "111") (name "unconnected-(JP1-Pad1)") (class "Default")
      (node (ref "JP1") (pin "1") (pinfunction "1_1") (pintype "passive"))
    )
    (net (code "112") (name "unconnected-(JP1-Pad2)") (class "Default")
      (node (ref "JP1") (pin "2") (pinfunction "2_2") (pintype "passive"))
    )
    (net (code "113") (name "unconnected-(U1-0(RX0)-Pad0)") (class "Default")
      (node (ref "U1") (pin "0") (pinfunction "0(RX0)_0") (pintype "bidirectional"))
    )
    (net (code "114") (name "unconnected-(U1-1(TX0)-Pad1)") (class "Default")
      (node (ref "U1") (pin "1") (pinfunction "1(TX0)_1") (pintype "bidirectional"))
    )
    (net (code "115") (name "unconnected-(U1-A0(RX0)-PadA0)") (class "Default")
      (node (ref "U1") (pin "A0") (pinfunction "A0(RX0)_A0") (pintype "bidirectional"))
    )
    (net (code "116") (name "unconnected-(U1-A1(TX0)-PadA1)") (class "Default")
      (node (ref "U1") (pin "A1") (pinfunction "A1(TX0)_A1") (pintype "bidirectional"))
    )
    (net (code "117") (name "unconnected-(U1-Pad10)") (class "Default")
      (node (ref "U1") (pin "10") (pinfunction "10_10") (pintype "bidirectional"))
    )
    (net (code "118") (name "unconnected-(U1-Pad11)") (class "Default")
      (node (ref "U1") (pin "11") (pinfunction "11_11") (pintype "bidirectional"))
    )
    (net (code "119") (name "unconnected-(U1-Pad12)") (class "Default")
      (node (ref "U1") (pin "12") (pinfunction "12_12") (pintype "bidirectional"))
    )
    (net (code "120") (name "unconnected-(U1-Pad13)") (class "Default")
      (node (ref "U1") (pin "13") (pinfunction "13_13") (pintype "bidirectional"))
    )
    (net (code "121") (name "unconnected-(U1-Pad45)") (class "Default")
      (node (ref "U1") (pin "45") (pinfunction "45_45") (pintype "bidirectional"))
    )
    (net (code "122") (name "unconnected-(U1-Pad46)") (class "Default")
      (node (ref "U1") (pin "46") (pinfunction "46_46") (pintype "bidirectional"))
    )
    (net (code "123") (name "unconnected-(U1-PadA2)") (class "Default")
      (node (ref "U1") (pin "A2") (pinfunction "A2_A2") (pintype "bidirectional"))
    )
    (net (code "124") (name "unconnected-(U1-PadA3)") (class "Default")
      (node (ref "U1") (pin "A3") (pinfunction "A3_A3") (pintype "bidirectional"))
    )
    (net (code "125") (name "unconnected-(U1-PadA4)") (class "Default")
      (node (ref "U1") (pin "A4") (pinfunction "A4_A4") (pintype "bidirectional"))
    )
    (net (code "126") (name "unconnected-(U1-PadA5)") (class "Default")
      (node (ref "U1") (pin "A5") (pinfunction "A5_A5") (pintype "bidirectional"))
    )
    (net (code "127") (name "unconnected-(U1-PadA10)") (class "Default")
      (node (ref "U1") (pin "A10") (pinfunction "A10_A10") (pintype "bidirectional"))
    )
    (net (code "128") (name "unconnected-(U1-PadA11)") (class "Default")
      (node (ref "U1") (pin "A11") (pinfunction "A11_A11") (pintype "bidirectional"))
    )
    (net (code "129") (name "unconnected-(U1-PadA12)") (class "Default")
      (node (ref "U1") (pin "A12") (pinfunction "A12_A12") (pintype "bidirectional"))
    )
    (net (code "130") (name "unconnected-(U1-PadA13)") (class "Default")
      (node (ref "U1") (pin "A13") (pinfunction "A13_A13") (pintype "bidirectional"))
    )
    (net (code "131") (name "unconnected-(U1-PadA14)") (class "Default")
      (node (ref "U1") (pin "A14") (pinfunction "A14_A14") (pintype "bidirectional"))
    )
    (net (code "132") (name "unconnected-(U1-PadA15)") (class "Default")
      (node (ref "U1") (pin "A15") (pinfunction "A15_A15") (pintype "bidirectional"))
    )
    (net (code "133") (name "unconnected-(U1-PadAREF)") (class "Default")
      (node (ref "U1") (pin "AREF") (pinfunction "AREF_AREF") (pintype "bidirectional"))
    )
    (net (code "134") (name "unconnected-(U2-3A-Pad7)") (class "Default")
      (node (ref "U2") (pin "7") (pinfunction "3A_7") (pintype "bidirectional"))
    )
    (net (code "135") (name "unconnected-(U2-3Y-Pad6)") (class "Default")
      (node (ref "U2") (pin "6") (pinfunction "3Y_6") (pintype "bidirectional"))
    )
    (net (code "136") (name "unconnected-(U2-4A-Pad9)") (class "Default")
      (node (ref "U2") (pin "9") (pinfunction "4A_9") (pintype "bidirectional"))
    )
    (net (code "137") (name "unconnected-(U2-4Y-Pad10)") (class "Default")
      (node (ref "U2") (pin "10") (pinfunction "4Y_10") (pintype "bidirectional"))
    )
    (net (code "138") (name "unconnected-(U6-5A-Pad11)") (class "Default")
      (node (ref "U6") (pin "11") (pinfunction "5A_11") (pintype "bidirectional"))
    )
    (net (code "139") (name "unconnected-(U6-5Y-Pad12)") (class "Default")
      (node (ref "U6") (pin "12") (pinfunction "5Y_12") (pintype "bidirectional"))
    )
    (net (code "140") (name "unconnected-(UART1-Pad1)") (class "Default")
      (node (ref "UART1") (pin "1") (pinfunction "1_1") (pintype "passive"))
    )
    (net (code "141") (name "unconnected-(UART1-Pad4)") (class "Default")
      (node (ref "UART1") (pin "4") (pinfunction "4_4") (pintype "passive"))
    )
    (net (code "142") (name "unconnected-(UART1-Pad6)") (class "Default")
      (node (ref "UART1") (pin "6") (pinfunction "6_6") (pintype "passive"))
    )
    (net (code "143") (name "unconnected-(UART1-Pad7)") (class "Default")
      (node (ref "UART1") (pin "7") (pinfunction "7_7") (pintype "passive"))
    )
    (net (code "144") (name "unconnected-(UART1-Pad8)") (class "Default")
      (node (ref "UART1") (pin "8") (pinfunction "8_8") (pintype "passive"))
    )
    (net (code "145") (name "unconnected-(UART2-Pad1)") (class "Default")
      (node (ref "UART2") (pin "1") (pinfunction "1_1") (pintype "passive"))
    )
    (net (code "146") (name "unconnected-(UART2-Pad4)") (class "Default")
      (node (ref "UART2") (pin "4") (pinfunction "4_4") (pintype "passive"))
    )
    (net (code "147") (name "unconnected-(UART2-Pad6)") (class "Default")
      (node (ref "UART2") (pin "6") (pinfunction "6_6") (pintype "passive"))
    )
    (net (code "148") (name "unconnected-(UART2-Pad7)") (class "Default")
      (node (ref "UART2") (pin "7") (pinfunction "7_7") (pintype "passive"))
    )
    (net (code "149") (name "unconnected-(UART2-Pad8)") (class "Default")
      (node (ref "UART2") (pin "8") (pinfunction "8_8") (pintype "passive"))
    )
    (net (code "150") (name "unconnected-(UART3-Pad1)") (class "Default")
      (node (ref "UART3") (pin "1") (pinfunction "1_1") (pintype "passive"))
    )
    (net (code "151") (name "unconnected-(UART3-Pad4)") (class "Default")
      (node (ref "UART3") (pin "4") (pinfunction "4_4") (pintype "passive"))
    )
    (net (code "152") (name "unconnected-(UART3-Pad6)") (class "Default")
      (node (ref "UART3") (pin "6") (pinfunction "6_6") (pintype "passive"))
    )
    (net (code "153") (name "unconnected-(UART3-Pad7)") (class "Default")
      (node (ref "UART3") (pin "7") (pinfunction "7_7") (pintype "passive"))
    )
    (net (code "154") (name "unconnected-(UART3-Pad8)") (class "Default")
      (node (ref "UART3") (pin "8") (pinfunction "8_8") (pintype "passive"))
    )
  )
)
